# Power.net
KiCad netlist of a schematic drawn in Altium Designer
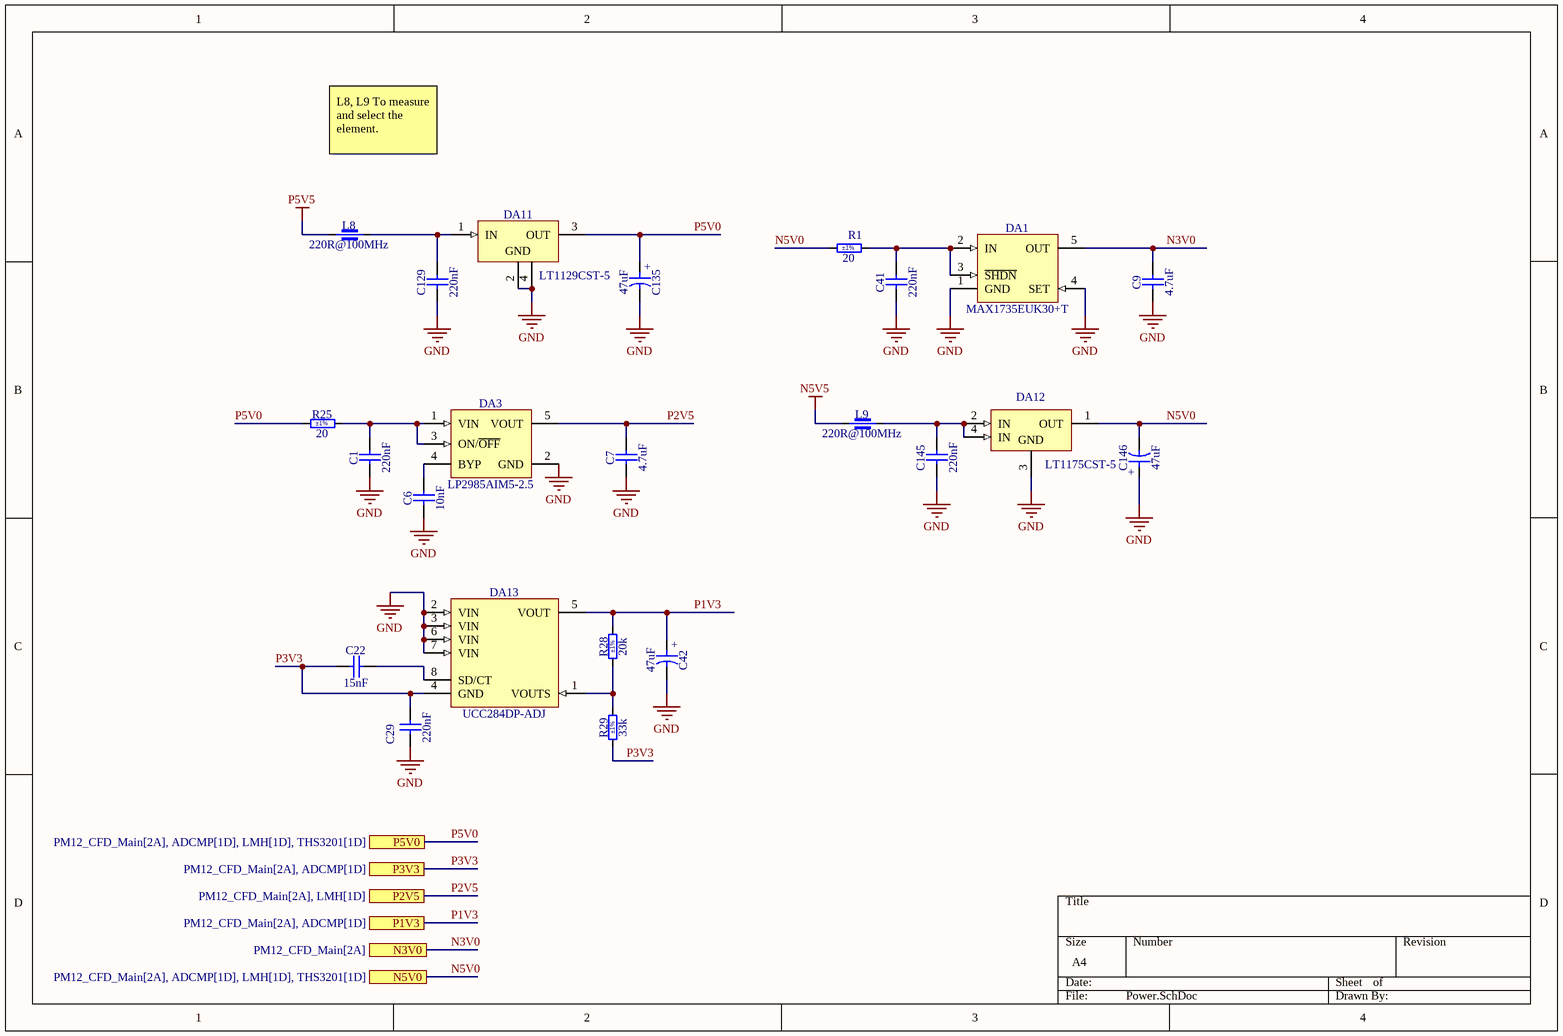
[diagram p0: Power.SchDoc]

(export (version "E")
  (design (tool "Eeschema 10.0.6"))
  (components
    (comp (ref "C1")
      (value "220nF")
      (footprint "CAPC2012X135N")
      (description "Non-polarised capacitor")
      (fields
        (field (name "PART NUMBER") "CC0805_220NF_50V_10%_X7R")
        (field (name "VOLTAGE") "50V")
        (field (name "AUTHOR") "CERN DEM JLC")
      )
      (libsource (lib "Capacitors") (part "Capacitor - non polarized"))
    )
    (comp (ref "C6")
      (value "10nF")
      (footprint "CAPC2012X135N")
      (description "Non-polarised capacitor")
      (fields
        (field (name "PART NUMBER") "CC0805_10NF_50V_5%_C0G")
        (field (name "VOLTAGE") "50V")
        (field (name "AUTHOR") "CERN DEM JLC")
      )
      (libsource (lib "Capacitors") (part "Capacitor - non polarized"))
    )
    (comp (ref "C7")
      (value "4.7uF")
      (footprint "CAPC2012X135N")
      (description "Non-polarised capacitor")
      (fields
        (field (name "PART NUMBER") "CC0805_4.7UF_16V_10%_X7R")
        (field (name "VOLTAGE") "16V")
        (field (name "AUTHOR") "CERN DEM JLC")
      )
      (libsource (lib "Capacitors") (part "Capacitor - non polarized"))
    )
    (comp (ref "C9")
      (value "4.7uF")
      (footprint "CAPC2012X135N")
      (description "Non-polarised capacitor")
      (fields
        (field (name "PART NUMBER") "CC0805_4.7UF_16V_10%_X7R")
        (field (name "VOLTAGE") "16V")
        (field (name "AUTHOR") "CERN DEM JLC")
      )
      (libsource (lib "Capacitors") (part "Capacitor - non polarized"))
    )
    (comp (ref "C22")
      (value "15nF")
      (footprint "CAPC2012X135N")
      (description "Non-polarised capacitor")
      (fields
        (field (name "PART NUMBER") "CC0805_15NF_50V_10%_X7R")
        (field (name "VOLTAGE") "50V")
        (field (name "AUTHOR") "CERN DEM JLC")
      )
      (libsource (lib "Capacitors") (part "Capacitor - non polarized"))
    )
    (comp (ref "C29")
      (value "220nF")
      (footprint "CAPC2012X135N")
      (description "Non-polarised capacitor")
      (fields
        (field (name "PART NUMBER") "CC0805_220NF_50V_10%_X7R")
        (field (name "VOLTAGE") "50V")
        (field (name "AUTHOR") "CERN DEM JLC")
      )
      (libsource (lib "Capacitors") (part "Capacitor - non polarized"))
    )
    (comp (ref "C41")
      (value "220nF")
      (footprint "CAPC2012X135N")
      (description "Non-polarised capacitor")
      (fields
        (field (name "PART NUMBER") "CC0805_220NF_50V_10%_X7R")
        (field (name "VOLTAGE") "50V")
        (field (name "AUTHOR") "CERN DEM JLC")
      )
      (libsource (lib "Capacitors") (part "Capacitor - non polarized"))
    )
    (comp (ref "C42")
      (value "47uF")
      (footprint "CAPAE530X610N")
      (description "Polarised capacitor")
      (fields
        (field (name "PART NUMBER") "CAE530-610_47UF_16V_20%")
        (field (name "VOLTAGE") "16V")
        (field (name "AUTHOR") "CERN DEM HF")
      )
      (libsource (lib "Capacitors") (part "Capacitor - polarized"))
    )
    (comp (ref "C129")
      (value "220nF")
      (footprint "CAPC2012X135N")
      (description "Non-polarised capacitor")
      (fields
        (field (name "PART NUMBER") "CC0805_220NF_50V_10%_X7R")
        (field (name "VOLTAGE") "50V")
        (field (name "AUTHOR") "CERN DEM JLC")
      )
      (libsource (lib "Capacitors") (part "Capacitor - non polarized"))
    )
    (comp (ref "C135")
      (value "47uF")
      (footprint "CAPAE530X610N")
      (description "Polarised capacitor")
      (fields
        (field (name "PART NUMBER") "CAE530-610_47UF_16V_20%")
        (field (name "VOLTAGE") "16V")
        (field (name "AUTHOR") "CERN DEM HF")
      )
      (libsource (lib "Capacitors") (part "Capacitor - polarized"))
    )
    (comp (ref "C145")
      (value "220nF")
      (footprint "CAPC2012X135N")
      (description "Non-polarised capacitor")
      (fields
        (field (name "PART NUMBER") "CC0805_220NF_50V_10%_X7R")
        (field (name "VOLTAGE") "50V")
        (field (name "AUTHOR") "CERN DEM JLC")
      )
      (libsource (lib "Capacitors") (part "Capacitor - non polarized"))
    )
    (comp (ref "C146")
      (value "47uF")
      (footprint "CAPAE530X610N")
      (description "Polarised capacitor")
      (fields
        (field (name "PART NUMBER") "CAE530-610_47UF_16V_20%")
        (field (name "VOLTAGE") "16V")
        (field (name "AUTHOR") "CERN DEM HF")
      )
      (libsource (lib "Capacitors") (part "Capacitor - polarized"))
    )
    (comp (ref "DA1")
      (value "MAX1735EUK30+T")
      (footprint "SOT95P280X145-5N")
      (description "200mA, Negative-Output, Low-Dropout Linear Regulator")
      (fields
        (field (name "MANUFACTURER") "MAXIM")
        (field (name "MANUFACTURER PART NUMBER") "MAX1735EUK30")
        (field (name "AUTHOR") "CERN DEM JLC")
      )
      (libsource (lib "ICs And Semiconductors") (part "MAX1735"))
    )
    (comp (ref "DA3")
      (value "LP2985AIM5-2.5")
      (footprint "SOT95P280X145-5N")
      (description "150mA Low-Noise Low-Dropout Regulator Whit Shutdown")
      (fields (field (name "MANUFACTURER") "TEXAS INSTRUMENTS") (field (name "AUTHOR") "CERN DEM HF"))
      (libsource (lib "ICs And Semiconductors") (part "LP2985"))
    )
    (comp (ref "DA11")
      (value "LT1129CST-5")
      (footprint "SOT230P700X180-4N")
      (description "3-Terminal Regulator 1=IN 2=GND 3=OUT 4=GND")
      (fields (field (name "MANUFACTURER") "LINEAR TECHNOLOGY") (field (name "AUTHOR") "CERN DEM HF"))
      (libsource (lib "ICs And Semiconductors") (part "REG3+1 1IN-2GND-3OUT+4GND"))
    )
    (comp (ref "DA12")
      (value "LT1175CST-5")
      (footprint "SOT230P700X180-4N")
      (description "3-Terminal Regulator 1=OUT 2=IN 3=GND 4=IN")
      (fields (field (name "MANUFACTURER") "LINEAR TECHNOLOGY") (field (name "AUTHOR") "CERN DEM HF"))
      (libsource (lib "ICs And Semiconductors") (part "REG3+1 1OUT-2IN-3GND+4IN"))
    )
    (comp (ref "DA13")
      (value "UCC284DP-ADJ")
      (footprint "SOIC127P600X175-8N")
      (description "5V, 500mA Low-Dropout Negative Linear Regulator")
      (fields (field (name "MANUFACTURER") "TEXAS INSTRUMENTS") (field (name "AUTHOR") "CERN DEM BR"))
      (libsource (lib "ICs And Semiconductors") (part "UCC284"))
    )
    (comp (ref "L8")
      (value "220R@100MHz")
      (footprint "INDC2012X105N")
      (fields
        (field (name "PART NUMBER") "IND0805_TDK_MPZ2012S221A")
        (field (name "POWER") "3A")
        (field (name "TOLERANCE") "±25%")
        (field (name "AUTHOR") "CERN DEM HF")
      )
      (libsource (lib "Inductors & Transformers") (part "Ferrite Bead"))
    )
    (comp (ref "L9")
      (value "220R@100MHz")
      (footprint "INDC2012X105N")
      (fields
        (field (name "PART NUMBER") "IND0805_TDK_MPZ2012S221A")
        (field (name "POWER") "3A")
        (field (name "TOLERANCE") "±25%")
        (field (name "AUTHOR") "CERN DEM HF")
      )
      (libsource (lib "Inductors & Transformers") (part "Ferrite Bead"))
    )
    (comp (ref "R1")
      (value "20")
      (footprint "RESC2012X60N")
      (description "Resistor - 1%")
      (fields
        (field (name "TOLERANCE") "±1%")
        (field (name "PART NUMBER") "R0805_20R_1%_0.125W_100PPM")
        (field (name "POWER") "0.125W")
        (field (name "AUTHOR") "CERN DEM JLC")
      )
      (libsource (lib "Resistors") (part "Resistor - 1%"))
    )
    (comp (ref "R25")
      (value "20")
      (footprint "RESC2012X60N")
      (description "Resistor - 1%")
      (fields
        (field (name "TOLERANCE") "±1%")
        (field (name "PART NUMBER") "R0805_20R_1%_0.125W_100PPM")
        (field (name "POWER") "0.125W")
        (field (name "AUTHOR") "CERN DEM JLC")
      )
      (libsource (lib "Resistors") (part "Resistor - 1%"))
    )
    (comp (ref "R28")
      (value "20k")
      (footprint "RESC2012X60N")
      (description "Resistor - 1%")
      (fields
        (field (name "TOLERANCE") "±1%")
        (field (name "PART NUMBER") "R0805_20K_1%_0.125W_100PPM")
        (field (name "POWER") "0.125W")
        (field (name "AUTHOR") "CERN DEM JLC")
      )
      (libsource (lib "Resistors") (part "Resistor - 1%"))
    )
    (comp (ref "R29")
      (value "33k")
      (footprint "RESC2012X60N")
      (description "Resistor - 1%")
      (fields
        (field (name "TOLERANCE") "±1%")
        (field (name "PART NUMBER") "R0805_33K_1%_0.125W_100PPM")
        (field (name "POWER") "0.125W")
        (field (name "AUTHOR") "CERN DEM JLC")
      )
      (libsource (lib "Resistors") (part "Resistor - 1%"))
    )
  )
  (nets
    (net (code "1") (name "/N3V0") (class "Default")
      (node (ref "C9") (pin "2") (pinfunction "2_2") (pintype "passive"))
      (node (ref "DA1") (pin "5") (pinfunction "OUT_5") (pintype "power_in"))
    )
    (net (code "2") (name "/N5V0") (class "Default")
      (node (ref "C146") (pin "2") (pinfunction "2_2") (pintype "passive"))
      (node (ref "DA12") (pin "1") (pinfunction "OUT_1") (pintype "power_in"))
      (node (ref "R1") (pin "1") (pinfunction "1_1") (pintype "passive"))
    )
    (net (code "3") (name "/P1V3") (class "Default")
      (node (ref "C42") (pin "1") (pinfunction "1_1") (pintype "passive"))
      (node (ref "DA13") (pin "5") (pinfunction "VOUT_5") (pintype "power_in"))
      (node (ref "R28") (pin "2") (pinfunction "2_2") (pintype "passive"))
    )
    (net (code "4") (name "/P2V5") (class "Default")
      (node (ref "C7") (pin "2") (pinfunction "2_2") (pintype "passive"))
      (node (ref "DA3") (pin "5") (pinfunction "VOUT_5") (pintype "power_in"))
    )
    (net (code "5") (name "/P3V3") (class "Default")
      (node (ref "C22") (pin "1") (pinfunction "1_1") (pintype "passive"))
      (node (ref "C29") (pin "2") (pinfunction "2_2") (pintype "passive"))
      (node (ref "DA13") (pin "4") (pinfunction "GND_4") (pintype "power_in"))
      (node (ref "R29") (pin "1") (pinfunction "1_1") (pintype "passive"))
    )
    (net (code "6") (name "/P5V0") (class "Default")
      (node (ref "C135") (pin "1") (pinfunction "1_1") (pintype "passive"))
      (node (ref "DA11") (pin "3") (pinfunction "OUT_3") (pintype "power_in"))
      (node (ref "R25") (pin "1") (pinfunction "1_1") (pintype "passive"))
    )
    (net (code "7") (name "GND") (class "Default")
      (node (ref "C1") (pin "1") (pinfunction "1_1") (pintype "passive"))
      (node (ref "C129") (pin "1") (pinfunction "1_1") (pintype "passive"))
      (node (ref "C135") (pin "2") (pinfunction "2_2") (pintype "passive"))
      (node (ref "C145") (pin "1") (pinfunction "1_1") (pintype "passive"))
      (node (ref "C146") (pin "1") (pinfunction "1_1") (pintype "passive"))
      (node (ref "C29") (pin "1") (pinfunction "1_1") (pintype "passive"))
      (node (ref "C41") (pin "1") (pinfunction "1_1") (pintype "passive"))
      (node (ref "C42") (pin "2") (pinfunction "2_2") (pintype "passive"))
      (node (ref "C6") (pin "1") (pinfunction "1_1") (pintype "passive"))
      (node (ref "C7") (pin "1") (pinfunction "1_1") (pintype "passive"))
      (node (ref "C9") (pin "1") (pinfunction "1_1") (pintype "passive"))
      (node (ref "DA1") (pin "1") (pinfunction "GND_1") (pintype "power_in"))
      (node (ref "DA1") (pin "4") (pinfunction "SET_4") (pintype "input"))
      (node (ref "DA11") (pin "2") (pinfunction "GND_2") (pintype "power_in"))
      (node (ref "DA11") (pin "4") (pinfunction "GND_4") (pintype "power_in"))
      (node (ref "DA12") (pin "3") (pinfunction "GND_3") (pintype "power_in"))
      (node (ref "DA13") (pin "2") (pinfunction "VIN_2") (pintype "input"))
      (node (ref "DA13") (pin "3") (pinfunction "VIN_3") (pintype "input"))
      (node (ref "DA13") (pin "6") (pinfunction "VIN_6") (pintype "input"))
      (node (ref "DA13") (pin "7") (pinfunction "VIN_7") (pintype "input"))
      (node (ref "DA3") (pin "2") (pinfunction "GND_2") (pintype "power_in"))
    )
    (net (code "8") (name "N5V5") (class "Default")
      (node (ref "L9") (pin "1") (pinfunction "1_1") (pintype "passive"))
    )
    (net (code "9") (name "Net-(C145-Pad2)") (class "Default")
      (node (ref "C145") (pin "2") (pinfunction "2_2") (pintype "passive"))
      (node (ref "DA12") (pin "2") (pinfunction "IN_2") (pintype "input"))
      (node (ref "DA12") (pin "4") (pinfunction "IN_4") (pintype "input"))
      (node (ref "L9") (pin "2") (pinfunction "2_2") (pintype "passive"))
    )
    (net (code "10") (name "Net-(DA1-IN)") (class "Default")
      (node (ref "C41") (pin "2") (pinfunction "2_2") (pintype "passive"))
      (node (ref "DA1") (pin "2") (pinfunction "IN_2") (pintype "input"))
      (node (ref "DA1") (pin "3") (pinfunction "~{SHDN}_3") (pintype "input"))
      (node (ref "R1") (pin "2") (pinfunction "2_2") (pintype "passive"))
    )
    (net (code "11") (name "Net-(DA3-BYP)") (class "Default")
      (node (ref "C6") (pin "2") (pinfunction "2_2") (pintype "passive"))
      (node (ref "DA3") (pin "4") (pinfunction "BYP_4") (pintype "passive"))
    )
    (net (code "12") (name "Net-(DA3-ON{slash}~{OFF})") (class "Default")
      (node (ref "C1") (pin "2") (pinfunction "2_2") (pintype "passive"))
      (node (ref "DA3") (pin "1") (pinfunction "VIN_1") (pintype "input"))
      (node (ref "DA3") (pin "3") (pinfunction "ON/~{OFF}_3") (pintype "input"))
      (node (ref "R25") (pin "2") (pinfunction "2_2") (pintype "passive"))
    )
    (net (code "13") (name "Net-(DA11-IN)") (class "Default")
      (node (ref "C129") (pin "2") (pinfunction "2_2") (pintype "passive"))
      (node (ref "DA11") (pin "1") (pinfunction "IN_1") (pintype "input"))
      (node (ref "L8") (pin "2") (pinfunction "2_2") (pintype "passive"))
    )
    (net (code "14") (name "Net-(DA13-SD{slash}CT)") (class "Default")
      (node (ref "C22") (pin "2") (pinfunction "2_2") (pintype "passive"))
      (node (ref "DA13") (pin "8") (pinfunction "SD/CT_8") (pintype "passive"))
    )
    (net (code "15") (name "Net-(DA13-VOUTS)") (class "Default")
      (node (ref "DA13") (pin "1") (pinfunction "VOUTS_1") (pintype "input"))
      (node (ref "R28") (pin "1") (pinfunction "1_1") (pintype "passive"))
      (node (ref "R29") (pin "2") (pinfunction "2_2") (pintype "passive"))
    )
    (net (code "16") (name "P5V5") (class "Default")
      (node (ref "L8") (pin "1") (pinfunction "1_1") (pintype "passive"))
    )
  )
)
